# 1-Schematic_Breadboard_Card.net
KiCad netlist of a schematic drawn in EasyEDA
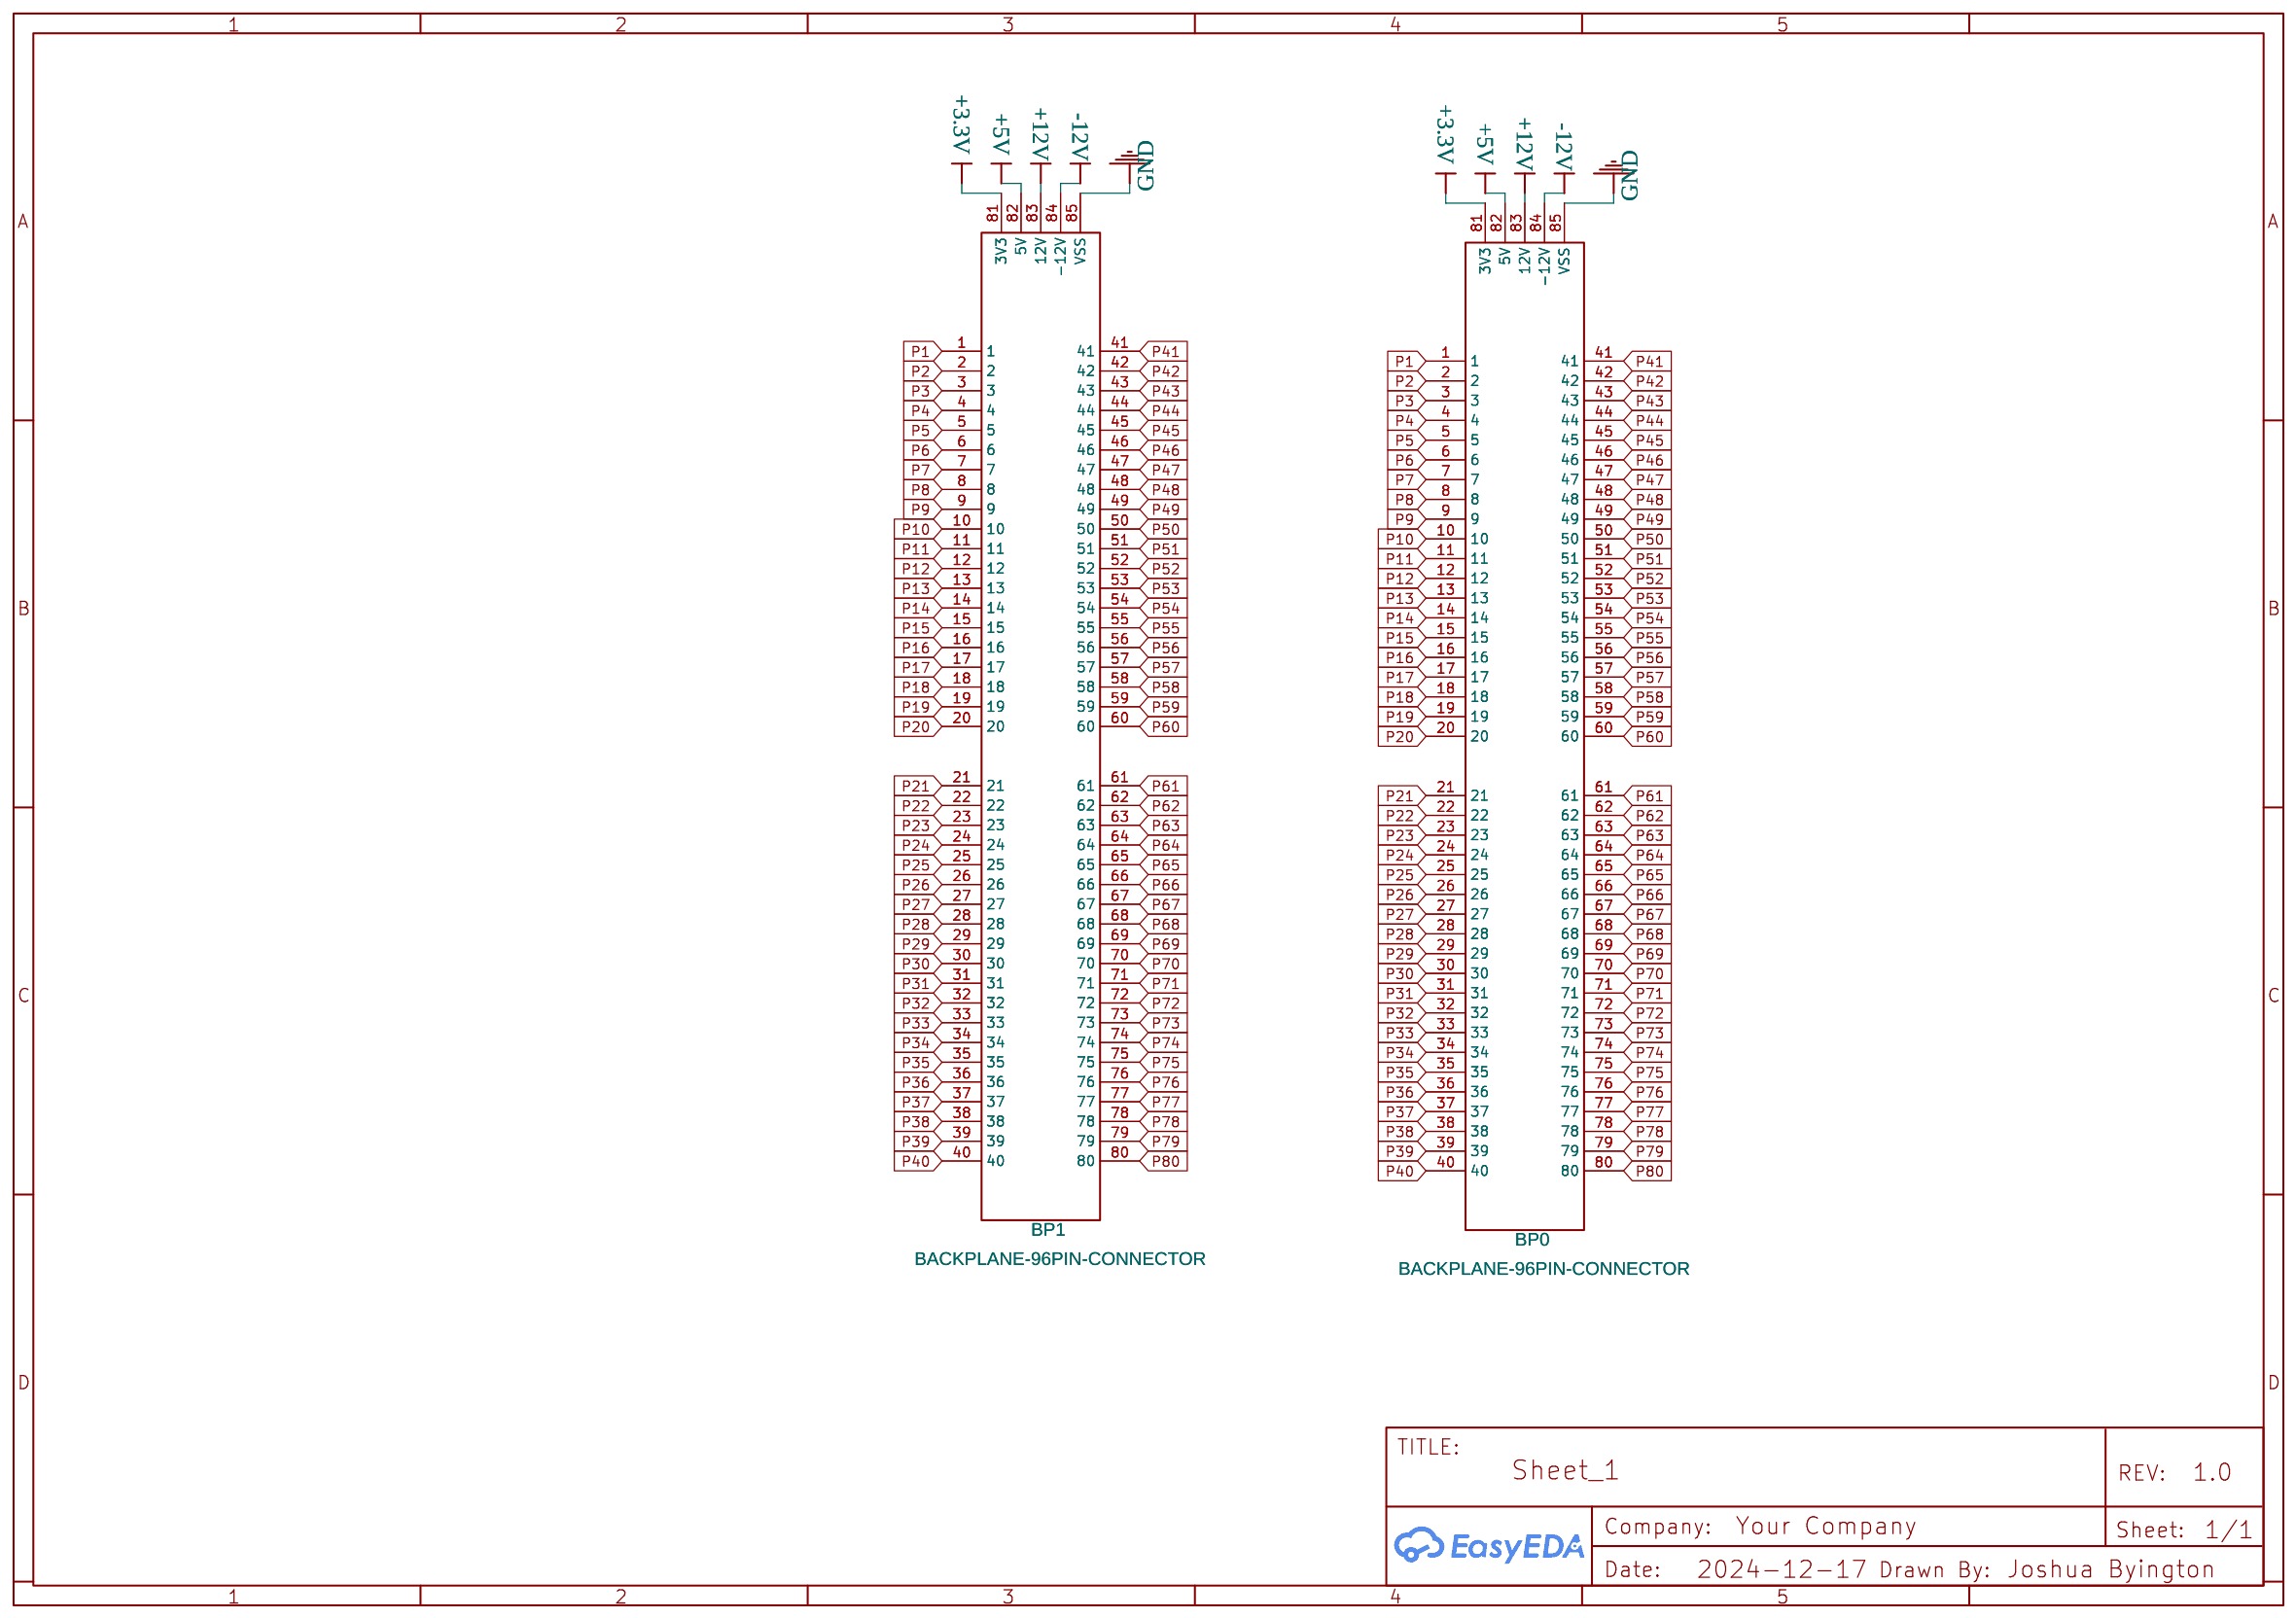
[diagram p0: schematic sheet]

(export (version "E")
  (design (tool "Eeschema 10.0.6"))
  (components
    (comp (ref "BP0")
      (value "BACKPLANE-96PIN-CONNECTOR")
      (libsource (lib "") (part "BACKPLANE-96PIN-CONNECTOR"))
    )
    (comp (ref "BP1")
      (value "BACKPLANE-96PIN-CONNECTOR")
      (libsource (lib "") (part "BACKPLANE-96PIN-CONNECTOR"))
    )
  )
  (nets
    (net (code "1") (name "+3.3V") (class "Default")
      (node (ref "BP0") (pin "81") (pinfunction "3V3_81") (pintype "unspecified"))
      (node (ref "BP1") (pin "81") (pinfunction "3V3_81") (pintype "unspecified"))
    )
    (net (code "2") (name "+5V") (class "Default")
      (node (ref "BP0") (pin "82") (pinfunction "5V_82") (pintype "unspecified"))
      (node (ref "BP1") (pin "82") (pinfunction "5V_82") (pintype "unspecified"))
    )
    (net (code "3") (name "+12V") (class "Default")
      (node (ref "BP0") (pin "83") (pinfunction "12V_83") (pintype "unspecified"))
      (node (ref "BP1") (pin "83") (pinfunction "12V_83") (pintype "unspecified"))
    )
    (net (code "4") (name "-12V") (class "Default")
      (node (ref "BP0") (pin "84") (pinfunction "-12V_84") (pintype "unspecified"))
      (node (ref "BP1") (pin "84") (pinfunction "-12V_84") (pintype "unspecified"))
    )
    (net (code "5") (name "GND") (class "Default")
      (node (ref "BP0") (pin "85") (pinfunction "VSS_85") (pintype "unspecified"))
      (node (ref "BP1") (pin "85") (pinfunction "VSS_85") (pintype "unspecified"))
    )
    (net (code "6") (name "P1") (class "Default")
      (node (ref "BP0") (pin "1") (pinfunction "1_1") (pintype "unspecified"))
      (node (ref "BP1") (pin "1") (pinfunction "1_1") (pintype "unspecified"))
    )
    (net (code "7") (name "P2") (class "Default")
      (node (ref "BP0") (pin "2") (pinfunction "2_2") (pintype "unspecified"))
      (node (ref "BP1") (pin "2") (pinfunction "2_2") (pintype "unspecified"))
    )
    (net (code "8") (name "P3") (class "Default")
      (node (ref "BP0") (pin "3") (pinfunction "3_3") (pintype "unspecified"))
      (node (ref "BP1") (pin "3") (pinfunction "3_3") (pintype "unspecified"))
    )
    (net (code "9") (name "P4") (class "Default")
      (node (ref "BP0") (pin "4") (pinfunction "4_4") (pintype "unspecified"))
      (node (ref "BP1") (pin "4") (pinfunction "4_4") (pintype "unspecified"))
    )
    (net (code "10") (name "P5") (class "Default")
      (node (ref "BP0") (pin "5") (pinfunction "5_5") (pintype "unspecified"))
      (node (ref "BP1") (pin "5") (pinfunction "5_5") (pintype "unspecified"))
    )
    (net (code "11") (name "P6") (class "Default")
      (node (ref "BP0") (pin "6") (pinfunction "6_6") (pintype "unspecified"))
      (node (ref "BP1") (pin "6") (pinfunction "6_6") (pintype "unspecified"))
    )
    (net (code "12") (name "P7") (class "Default")
      (node (ref "BP0") (pin "7") (pinfunction "7_7") (pintype "unspecified"))
      (node (ref "BP1") (pin "7") (pinfunction "7_7") (pintype "unspecified"))
    )
    (net (code "13") (name "P8") (class "Default")
      (node (ref "BP0") (pin "8") (pinfunction "8_8") (pintype "unspecified"))
      (node (ref "BP1") (pin "8") (pinfunction "8_8") (pintype "unspecified"))
    )
    (net (code "14") (name "P9") (class "Default")
      (node (ref "BP0") (pin "9") (pinfunction "9_9") (pintype "unspecified"))
      (node (ref "BP1") (pin "9") (pinfunction "9_9") (pintype "unspecified"))
    )
    (net (code "15") (name "P10") (class "Default")
      (node (ref "BP0") (pin "10") (pinfunction "10_10") (pintype "unspecified"))
      (node (ref "BP1") (pin "10") (pinfunction "10_10") (pintype "unspecified"))
    )
    (net (code "16") (name "P11") (class "Default")
      (node (ref "BP0") (pin "11") (pinfunction "11_11") (pintype "unspecified"))
      (node (ref "BP1") (pin "11") (pinfunction "11_11") (pintype "unspecified"))
    )
    (net (code "17") (name "P12") (class "Default")
      (node (ref "BP0") (pin "12") (pinfunction "12_12") (pintype "unspecified"))
      (node (ref "BP1") (pin "12") (pinfunction "12_12") (pintype "unspecified"))
    )
    (net (code "18") (name "P13") (class "Default")
      (node (ref "BP0") (pin "13") (pinfunction "13_13") (pintype "unspecified"))
      (node (ref "BP1") (pin "13") (pinfunction "13_13") (pintype "unspecified"))
    )
    (net (code "19") (name "P14") (class "Default")
      (node (ref "BP0") (pin "14") (pinfunction "14_14") (pintype "unspecified"))
      (node (ref "BP1") (pin "14") (pinfunction "14_14") (pintype "unspecified"))
    )
    (net (code "20") (name "P15") (class "Default")
      (node (ref "BP0") (pin "15") (pinfunction "15_15") (pintype "unspecified"))
      (node (ref "BP1") (pin "15") (pinfunction "15_15") (pintype "unspecified"))
    )
    (net (code "21") (name "P16") (class "Default")
      (node (ref "BP0") (pin "16") (pinfunction "16_16") (pintype "unspecified"))
      (node (ref "BP1") (pin "16") (pinfunction "16_16") (pintype "unspecified"))
    )
    (net (code "22") (name "P17") (class "Default")
      (node (ref "BP0") (pin "17") (pinfunction "17_17") (pintype "unspecified"))
      (node (ref "BP1") (pin "17") (pinfunction "17_17") (pintype "unspecified"))
    )
    (net (code "23") (name "P18") (class "Default")
      (node (ref "BP0") (pin "18") (pinfunction "18_18") (pintype "unspecified"))
      (node (ref "BP1") (pin "18") (pinfunction "18_18") (pintype "unspecified"))
    )
    (net (code "24") (name "P19") (class "Default")
      (node (ref "BP0") (pin "19") (pinfunction "19_19") (pintype "unspecified"))
      (node (ref "BP1") (pin "19") (pinfunction "19_19") (pintype "unspecified"))
    )
    (net (code "25") (name "P20") (class "Default")
      (node (ref "BP0") (pin "20") (pinfunction "20_20") (pintype "unspecified"))
      (node (ref "BP1") (pin "20") (pinfunction "20_20") (pintype "unspecified"))
    )
    (net (code "26") (name "P21") (class "Default")
      (node (ref "BP0") (pin "21") (pinfunction "21_21") (pintype "unspecified"))
      (node (ref "BP1") (pin "21") (pinfunction "21_21") (pintype "unspecified"))
    )
    (net (code "27") (name "P22") (class "Default")
      (node (ref "BP0") (pin "22") (pinfunction "22_22") (pintype "unspecified"))
      (node (ref "BP1") (pin "22") (pinfunction "22_22") (pintype "unspecified"))
    )
    (net (code "28") (name "P23") (class "Default")
      (node (ref "BP0") (pin "23") (pinfunction "23_23") (pintype "unspecified"))
      (node (ref "BP1") (pin "23") (pinfunction "23_23") (pintype "unspecified"))
    )
    (net (code "29") (name "P24") (class "Default")
      (node (ref "BP0") (pin "24") (pinfunction "24_24") (pintype "unspecified"))
      (node (ref "BP1") (pin "24") (pinfunction "24_24") (pintype "unspecified"))
    )
    (net (code "30") (name "P25") (class "Default")
      (node (ref "BP0") (pin "25") (pinfunction "25_25") (pintype "unspecified"))
      (node (ref "BP1") (pin "25") (pinfunction "25_25") (pintype "unspecified"))
    )
    (net (code "31") (name "P26") (class "Default")
      (node (ref "BP0") (pin "26") (pinfunction "26_26") (pintype "unspecified"))
      (node (ref "BP1") (pin "26") (pinfunction "26_26") (pintype "unspecified"))
    )
    (net (code "32") (name "P27") (class "Default")
      (node (ref "BP0") (pin "27") (pinfunction "27_27") (pintype "unspecified"))
      (node (ref "BP1") (pin "27") (pinfunction "27_27") (pintype "unspecified"))
    )
    (net (code "33") (name "P28") (class "Default")
      (node (ref "BP0") (pin "28") (pinfunction "28_28") (pintype "unspecified"))
      (node (ref "BP1") (pin "28") (pinfunction "28_28") (pintype "unspecified"))
    )
    (net (code "34") (name "P29") (class "Default")
      (node (ref "BP0") (pin "29") (pinfunction "29_29") (pintype "unspecified"))
      (node (ref "BP1") (pin "29") (pinfunction "29_29") (pintype "unspecified"))
    )
    (net (code "35") (name "P30") (class "Default")
      (node (ref "BP0") (pin "30") (pinfunction "30_30") (pintype "unspecified"))
      (node (ref "BP1") (pin "30") (pinfunction "30_30") (pintype "unspecified"))
    )
    (net (code "36") (name "P31") (class "Default")
      (node (ref "BP0") (pin "31") (pinfunction "31_31") (pintype "unspecified"))
      (node (ref "BP1") (pin "31") (pinfunction "31_31") (pintype "unspecified"))
    )
    (net (code "37") (name "P32") (class "Default")
      (node (ref "BP0") (pin "32") (pinfunction "32_32") (pintype "unspecified"))
      (node (ref "BP1") (pin "32") (pinfunction "32_32") (pintype "unspecified"))
    )
    (net (code "38") (name "P33") (class "Default")
      (node (ref "BP0") (pin "33") (pinfunction "33_33") (pintype "unspecified"))
      (node (ref "BP1") (pin "33") (pinfunction "33_33") (pintype "unspecified"))
    )
    (net (code "39") (name "P34") (class "Default")
      (node (ref "BP0") (pin "34") (pinfunction "34_34") (pintype "unspecified"))
      (node (ref "BP1") (pin "34") (pinfunction "34_34") (pintype "unspecified"))
    )
    (net (code "40") (name "P35") (class "Default")
      (node (ref "BP0") (pin "35") (pinfunction "35_35") (pintype "unspecified"))
      (node (ref "BP1") (pin "35") (pinfunction "35_35") (pintype "unspecified"))
    )
    (net (code "41") (name "P36") (class "Default")
      (node (ref "BP0") (pin "36") (pinfunction "36_36") (pintype "unspecified"))
      (node (ref "BP1") (pin "36") (pinfunction "36_36") (pintype "unspecified"))
    )
    (net (code "42") (name "P37") (class "Default")
      (node (ref "BP0") (pin "37") (pinfunction "37_37") (pintype "unspecified"))
      (node (ref "BP1") (pin "37") (pinfunction "37_37") (pintype "unspecified"))
    )
    (net (code "43") (name "P38") (class "Default")
      (node (ref "BP0") (pin "38") (pinfunction "38_38") (pintype "unspecified"))
      (node (ref "BP1") (pin "38") (pinfunction "38_38") (pintype "unspecified"))
    )
    (net (code "44") (name "P39") (class "Default")
      (node (ref "BP0") (pin "39") (pinfunction "39_39") (pintype "unspecified"))
      (node (ref "BP1") (pin "39") (pinfunction "39_39") (pintype "unspecified"))
    )
    (net (code "45") (name "P40") (class "Default")
      (node (ref "BP0") (pin "40") (pinfunction "40_40") (pintype "unspecified"))
      (node (ref "BP1") (pin "40") (pinfunction "40_40") (pintype "unspecified"))
    )
    (net (code "46") (name "P41") (class "Default")
      (node (ref "BP0") (pin "41") (pinfunction "41_41") (pintype "unspecified"))
      (node (ref "BP1") (pin "41") (pinfunction "41_41") (pintype "unspecified"))
    )
    (net (code "47") (name "P42") (class "Default")
      (node (ref "BP0") (pin "42") (pinfunction "42_42") (pintype "unspecified"))
      (node (ref "BP1") (pin "42") (pinfunction "42_42") (pintype "unspecified"))
    )
    (net (code "48") (name "P43") (class "Default")
      (node (ref "BP0") (pin "43") (pinfunction "43_43") (pintype "unspecified"))
      (node (ref "BP1") (pin "43") (pinfunction "43_43") (pintype "unspecified"))
    )
    (net (code "49") (name "P44") (class "Default")
      (node (ref "BP0") (pin "44") (pinfunction "44_44") (pintype "unspecified"))
      (node (ref "BP1") (pin "44") (pinfunction "44_44") (pintype "unspecified"))
    )
    (net (code "50") (name "P45") (class "Default")
      (node (ref "BP0") (pin "45") (pinfunction "45_45") (pintype "unspecified"))
      (node (ref "BP1") (pin "45") (pinfunction "45_45") (pintype "unspecified"))
    )
    (net (code "51") (name "P46") (class "Default")
      (node (ref "BP0") (pin "46") (pinfunction "46_46") (pintype "unspecified"))
      (node (ref "BP1") (pin "46") (pinfunction "46_46") (pintype "unspecified"))
    )
    (net (code "52") (name "P47") (class "Default")
      (node (ref "BP0") (pin "47") (pinfunction "47_47") (pintype "unspecified"))
      (node (ref "BP1") (pin "47") (pinfunction "47_47") (pintype "unspecified"))
    )
    (net (code "53") (name "P48") (class "Default")
      (node (ref "BP0") (pin "48") (pinfunction "48_48") (pintype "unspecified"))
      (node (ref "BP1") (pin "48") (pinfunction "48_48") (pintype "unspecified"))
    )
    (net (code "54") (name "P49") (class "Default")
      (node (ref "BP0") (pin "49") (pinfunction "49_49") (pintype "unspecified"))
      (node (ref "BP1") (pin "49") (pinfunction "49_49") (pintype "unspecified"))
    )
    (net (code "55") (name "P50") (class "Default")
      (node (ref "BP0") (pin "50") (pinfunction "50_50") (pintype "unspecified"))
      (node (ref "BP1") (pin "50") (pinfunction "50_50") (pintype "unspecified"))
    )
    (net (code "56") (name "P51") (class "Default")
      (node (ref "BP0") (pin "51") (pinfunction "51_51") (pintype "unspecified"))
      (node (ref "BP1") (pin "51") (pinfunction "51_51") (pintype "unspecified"))
    )
    (net (code "57") (name "P52") (class "Default")
      (node (ref "BP0") (pin "52") (pinfunction "52_52") (pintype "unspecified"))
      (node (ref "BP1") (pin "52") (pinfunction "52_52") (pintype "unspecified"))
    )
    (net (code "58") (name "P53") (class "Default")
      (node (ref "BP0") (pin "53") (pinfunction "53_53") (pintype "unspecified"))
      (node (ref "BP1") (pin "53") (pinfunction "53_53") (pintype "unspecified"))
    )
    (net (code "59") (name "P54") (class "Default")
      (node (ref "BP0") (pin "54") (pinfunction "54_54") (pintype "unspecified"))
      (node (ref "BP1") (pin "54") (pinfunction "54_54") (pintype "unspecified"))
    )
    (net (code "60") (name "P55") (class "Default")
      (node (ref "BP0") (pin "55") (pinfunction "55_55") (pintype "unspecified"))
      (node (ref "BP1") (pin "55") (pinfunction "55_55") (pintype "unspecified"))
    )
    (net (code "61") (name "P56") (class "Default")
      (node (ref "BP0") (pin "56") (pinfunction "56_56") (pintype "unspecified"))
      (node (ref "BP1") (pin "56") (pinfunction "56_56") (pintype "unspecified"))
    )
    (net (code "62") (name "P57") (class "Default")
      (node (ref "BP0") (pin "57") (pinfunction "57_57") (pintype "unspecified"))
      (node (ref "BP1") (pin "57") (pinfunction "57_57") (pintype "unspecified"))
    )
    (net (code "63") (name "P58") (class "Default")
      (node (ref "BP0") (pin "58") (pinfunction "58_58") (pintype "unspecified"))
      (node (ref "BP1") (pin "58") (pinfunction "58_58") (pintype "unspecified"))
    )
    (net (code "64") (name "P59") (class "Default")
      (node (ref "BP0") (pin "59") (pinfunction "59_59") (pintype "unspecified"))
      (node (ref "BP1") (pin "59") (pinfunction "59_59") (pintype "unspecified"))
    )
    (net (code "65") (name "P60") (class "Default")
      (node (ref "BP0") (pin "60") (pinfunction "60_60") (pintype "unspecified"))
      (node (ref "BP1") (pin "60") (pinfunction "60_60") (pintype "unspecified"))
    )
    (net (code "66") (name "P61") (class "Default")
      (node (ref "BP0") (pin "61") (pinfunction "61_61") (pintype "unspecified"))
      (node (ref "BP1") (pin "61") (pinfunction "61_61") (pintype "unspecified"))
    )
    (net (code "67") (name "P62") (class "Default")
      (node (ref "BP0") (pin "62") (pinfunction "62_62") (pintype "unspecified"))
      (node (ref "BP1") (pin "62") (pinfunction "62_62") (pintype "unspecified"))
    )
    (net (code "68") (name "P63") (class "Default")
      (node (ref "BP0") (pin "63") (pinfunction "63_63") (pintype "unspecified"))
      (node (ref "BP1") (pin "63") (pinfunction "63_63") (pintype "unspecified"))
    )
    (net (code "69") (name "P64") (class "Default")
      (node (ref "BP0") (pin "64") (pinfunction "64_64") (pintype "unspecified"))
      (node (ref "BP1") (pin "64") (pinfunction "64_64") (pintype "unspecified"))
    )
    (net (code "70") (name "P65") (class "Default")
      (node (ref "BP0") (pin "65") (pinfunction "65_65") (pintype "unspecified"))
      (node (ref "BP1") (pin "65") (pinfunction "65_65") (pintype "unspecified"))
    )
    (net (code "71") (name "P66") (class "Default")
      (node (ref "BP0") (pin "66") (pinfunction "66_66") (pintype "unspecified"))
      (node (ref "BP1") (pin "66") (pinfunction "66_66") (pintype "unspecified"))
    )
    (net (code "72") (name "P67") (class "Default")
      (node (ref "BP0") (pin "67") (pinfunction "67_67") (pintype "unspecified"))
      (node (ref "BP1") (pin "67") (pinfunction "67_67") (pintype "unspecified"))
    )
    (net (code "73") (name "P68") (class "Default")
      (node (ref "BP0") (pin "68") (pinfunction "68_68") (pintype "unspecified"))
      (node (ref "BP1") (pin "68") (pinfunction "68_68") (pintype "unspecified"))
    )
    (net (code "74") (name "P69") (class "Default")
      (node (ref "BP0") (pin "69") (pinfunction "69_69") (pintype "unspecified"))
      (node (ref "BP1") (pin "69") (pinfunction "69_69") (pintype "unspecified"))
    )
    (net (code "75") (name "P70") (class "Default")
      (node (ref "BP0") (pin "70") (pinfunction "70_70") (pintype "unspecified"))
      (node (ref "BP1") (pin "70") (pinfunction "70_70") (pintype "unspecified"))
    )
    (net (code "76") (name "P71") (class "Default")
      (node (ref "BP0") (pin "71") (pinfunction "71_71") (pintype "unspecified"))
      (node (ref "BP1") (pin "71") (pinfunction "71_71") (pintype "unspecified"))
    )
    (net (code "77") (name "P72") (class "Default")
      (node (ref "BP0") (pin "72") (pinfunction "72_72") (pintype "unspecified"))
      (node (ref "BP1") (pin "72") (pinfunction "72_72") (pintype "unspecified"))
    )
    (net (code "78") (name "P73") (class "Default")
      (node (ref "BP0") (pin "73") (pinfunction "73_73") (pintype "unspecified"))
      (node (ref "BP1") (pin "73") (pinfunction "73_73") (pintype "unspecified"))
    )
    (net (code "79") (name "P74") (class "Default")
      (node (ref "BP0") (pin "74") (pinfunction "74_74") (pintype "unspecified"))
      (node (ref "BP1") (pin "74") (pinfunction "74_74") (pintype "unspecified"))
    )
    (net (code "80") (name "P75") (class "Default")
      (node (ref "BP0") (pin "75") (pinfunction "75_75") (pintype "unspecified"))
      (node (ref "BP1") (pin "75") (pinfunction "75_75") (pintype "unspecified"))
    )
    (net (code "81") (name "P76") (class "Default")
      (node (ref "BP0") (pin "76") (pinfunction "76_76") (pintype "unspecified"))
      (node (ref "BP1") (pin "76") (pinfunction "76_76") (pintype "unspecified"))
    )
    (net (code "82") (name "P77") (class "Default")
      (node (ref "BP0") (pin "77") (pinfunction "77_77") (pintype "unspecified"))
      (node (ref "BP1") (pin "77") (pinfunction "77_77") (pintype "unspecified"))
    )
    (net (code "83") (name "P78") (class "Default")
      (node (ref "BP0") (pin "78") (pinfunction "78_78") (pintype "unspecified"))
      (node (ref "BP1") (pin "78") (pinfunction "78_78") (pintype "unspecified"))
    )
    (net (code "84") (name "P79") (class "Default")
      (node (ref "BP0") (pin "79") (pinfunction "79_79") (pintype "unspecified"))
      (node (ref "BP1") (pin "79") (pinfunction "79_79") (pintype "unspecified"))
    )
    (net (code "85") (name "P80") (class "Default")
      (node (ref "BP0") (pin "80") (pinfunction "80_80") (pintype "unspecified"))
      (node (ref "BP1") (pin "80") (pinfunction "80_80") (pintype "unspecified"))
    )
  )
)
